# M660X.net
KiCad netlist of a schematic drawn in EAGLE
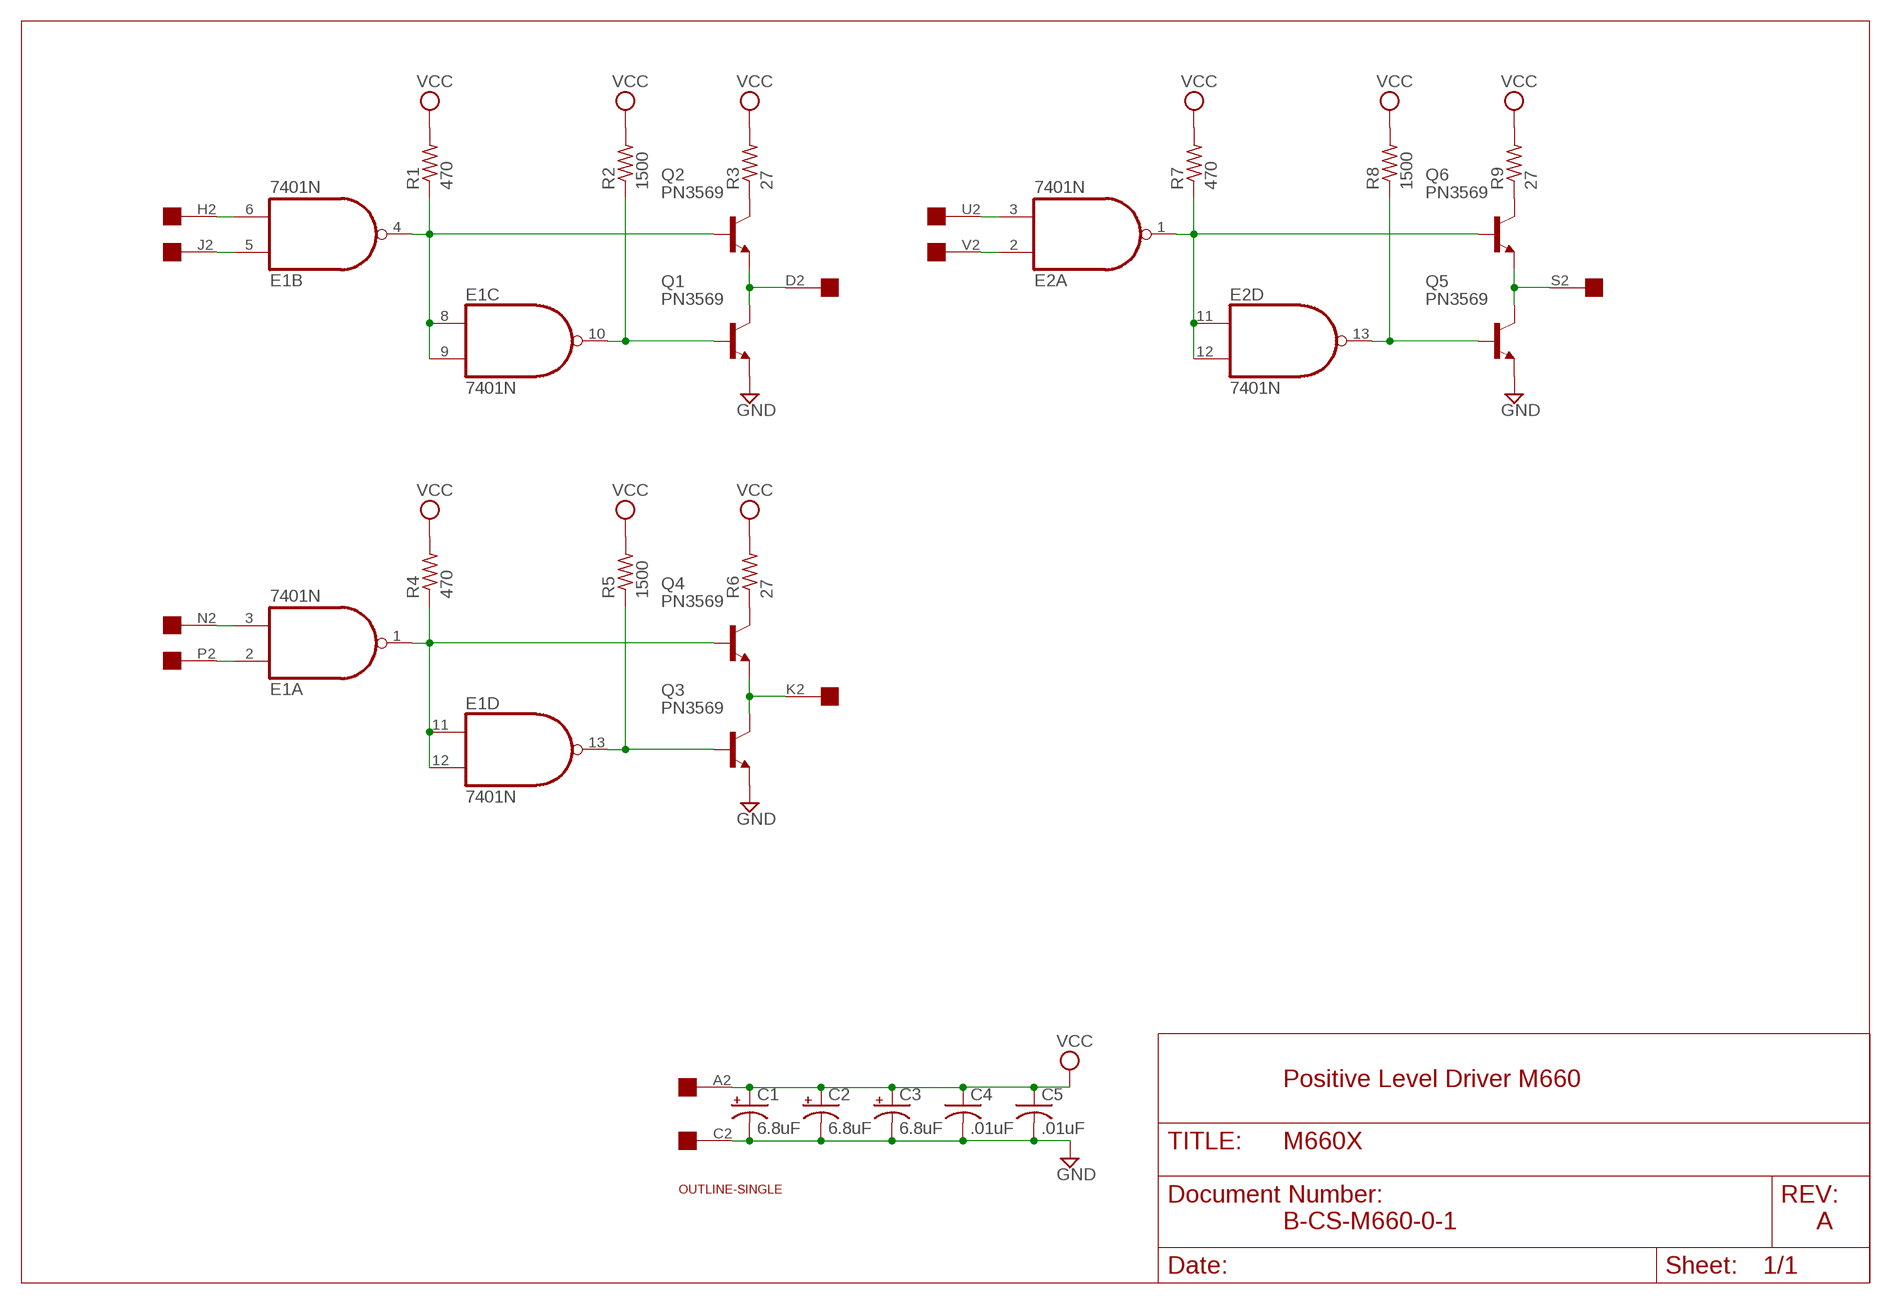
[diagram p0: schematic, sheet 1]

(export (version "E")
  (design (tool "Eeschema 10.0.6"))
  (components
    (comp (ref "C1")
      (value "6.8uF")
      (footprint "eagle-import:E15-5")
      (libsource (lib "eagle-import") (part "CPOL-USE15-5AXIAL"))
    )
    (comp (ref "C2")
      (value "6.8uF")
      (footprint "eagle-import:E15-5")
      (libsource (lib "eagle-import") (part "CPOL-USE15-5AXIAL"))
    )
    (comp (ref "C3")
      (value "6.8uF")
      (footprint "eagle-import:E15-5")
      (libsource (lib "eagle-import") (part "CPOL-USE15-5AXIAL"))
    )
    (comp (ref "C4")
      (value ".01uF")
      (footprint "eagle-import:C050-025X075")
      (libsource (lib "eagle-import") (part "C-US050-025X075"))
    )
    (comp (ref "C5")
      (value ".01uF")
      (footprint "eagle-import:C050-025X075")
      (libsource (lib "eagle-import") (part "C-US050-025X075"))
    )
    (comp (ref "E1")
      (value "7401N")
      (footprint "eagle-import:DIL14")
      (libsource (lib "eagle-import") (part "7401NLS"))
    )
    (comp (ref "E2")
      (value "7401N")
      (footprint "eagle-import:DIL14")
      (libsource (lib "eagle-import") (part "7401NLS"))
    )
    (comp (ref "Q1")
      (value "PN3569")
      (footprint "eagle-import:TO5")
      (libsource (lib "eagle-import") (part "2N2219"))
    )
    (comp (ref "Q2")
      (value "PN3569")
      (footprint "eagle-import:TO5")
      (libsource (lib "eagle-import") (part "2N2219"))
    )
    (comp (ref "Q3")
      (value "PN3569")
      (footprint "eagle-import:TO5")
      (libsource (lib "eagle-import") (part "2N2219"))
    )
    (comp (ref "Q4")
      (value "PN3569")
      (footprint "eagle-import:TO5")
      (libsource (lib "eagle-import") (part "2N2219"))
    )
    (comp (ref "Q5")
      (value "PN3569")
      (footprint "eagle-import:TO5")
      (libsource (lib "eagle-import") (part "2N2219"))
    )
    (comp (ref "Q6")
      (value "PN3569")
      (footprint "eagle-import:TO5")
      (libsource (lib "eagle-import") (part "2N2219"))
    )
    (comp (ref "R1")
      (value "470")
      (footprint "eagle-import:0207_10")
      (libsource (lib "eagle-import") (part "R-US_0207/10"))
    )
    (comp (ref "R2")
      (value "1500")
      (footprint "eagle-import:0207_10")
      (libsource (lib "eagle-import") (part "R-US_0207/10"))
    )
    (comp (ref "R3")
      (value "27")
      (footprint "eagle-import:0411_15")
      (libsource (lib "eagle-import") (part "R-US_0411/15"))
    )
    (comp (ref "R4")
      (value "470")
      (footprint "eagle-import:0207_10")
      (libsource (lib "eagle-import") (part "R-US_0207/10"))
    )
    (comp (ref "R5")
      (value "1500")
      (footprint "eagle-import:0207_10")
      (libsource (lib "eagle-import") (part "R-US_0207/10"))
    )
    (comp (ref "R6")
      (value "27")
      (footprint "eagle-import:0411_15")
      (libsource (lib "eagle-import") (part "R-US_0411/15"))
    )
    (comp (ref "R7")
      (value "470")
      (footprint "eagle-import:0207_10")
      (libsource (lib "eagle-import") (part "R-US_0207/10"))
    )
    (comp (ref "R8")
      (value "1500")
      (footprint "eagle-import:0207_10")
      (libsource (lib "eagle-import") (part "R-US_0207/10"))
    )
    (comp (ref "R9")
      (value "27")
      (footprint "eagle-import:0411_15")
      (libsource (lib "eagle-import") (part "R-US_0411/15"))
    )
    (comp (ref "U$1")
      (value "OUTLINE-SINGLE")
      (footprint "eagle-import:SINGLE")
      (libsource (lib "eagle-import") (part "OUTLINE-SINGLE"))
    )
    (comp (ref "U$3")
      (value "EDGE-1")
      (footprint "eagle-import:EDGE-CON1")
      (libsource (lib "eagle-import") (part "EDGE-1"))
    )
  )
  (nets
    (net (code "1") (name "GND") (class "Default")
      (node (ref "C1") (pin "-") (pinfunction "-_-") (pintype "passive"))
      (node (ref "C2") (pin "-") (pinfunction "-_-") (pintype "passive"))
      (node (ref "C3") (pin "-") (pinfunction "-_-") (pintype "passive"))
      (node (ref "C4") (pin "2") (pinfunction "2_2") (pintype "passive"))
      (node (ref "C5") (pin "2") (pinfunction "2_2") (pintype "passive"))
      (node (ref "Q1") (pin "1") (pinfunction "E_1") (pintype "passive"))
      (node (ref "Q3") (pin "1") (pinfunction "E_1") (pintype "passive"))
      (node (ref "Q5") (pin "1") (pinfunction "E_1") (pintype "passive"))
      (node (ref "U$3") (pin "C2") (pinfunction "1_C2") (pintype "bidirectional"))
    )
    (net (code "2") (name "Net-(E1A-I0)") (class "Default")
      (node (ref "E1") (pin "2") (pinfunction "I0_2") (pintype "input"))
      (node (ref "U$3") (pin "P2") (pinfunction "1_P2") (pintype "bidirectional"))
    )
    (net (code "3") (name "Net-(E1A-I1)") (class "Default")
      (node (ref "E1") (pin "3") (pinfunction "I1_3") (pintype "input"))
      (node (ref "U$3") (pin "N2") (pinfunction "1_N2") (pintype "bidirectional"))
    )
    (net (code "4") (name "Net-(E1A-O)") (class "Default")
      (node (ref "E1") (pin "1") (pinfunction "O_1") (pintype "open_collector"))
      (node (ref "E1") (pin "11") (pinfunction "I0_11") (pintype "input"))
      (node (ref "E1") (pin "12") (pinfunction "I1_12") (pintype "input"))
      (node (ref "Q4") (pin "2") (pinfunction "B_2") (pintype "passive"))
      (node (ref "R4") (pin "1") (pinfunction "1_1") (pintype "passive"))
    )
    (net (code "5") (name "Net-(E1B-I0)") (class "Default")
      (node (ref "E1") (pin "5") (pinfunction "I0_5") (pintype "input"))
      (node (ref "U$3") (pin "J2") (pinfunction "1_J2") (pintype "bidirectional"))
    )
    (net (code "6") (name "Net-(E1B-I1)") (class "Default")
      (node (ref "E1") (pin "6") (pinfunction "I1_6") (pintype "input"))
      (node (ref "U$3") (pin "H2") (pinfunction "1_H2") (pintype "bidirectional"))
    )
    (net (code "7") (name "Net-(E1B-O)") (class "Default")
      (node (ref "E1") (pin "4") (pinfunction "O_4") (pintype "open_collector"))
      (node (ref "E1") (pin "8") (pinfunction "I0_8") (pintype "input"))
      (node (ref "E1") (pin "9") (pinfunction "I1_9") (pintype "input"))
      (node (ref "Q2") (pin "2") (pinfunction "B_2") (pintype "passive"))
      (node (ref "R1") (pin "1") (pinfunction "1_1") (pintype "passive"))
    )
    (net (code "8") (name "Net-(E1C-O)") (class "Default")
      (node (ref "E1") (pin "10") (pinfunction "O_10") (pintype "open_collector"))
      (node (ref "Q1") (pin "2") (pinfunction "B_2") (pintype "passive"))
      (node (ref "R2") (pin "1") (pinfunction "1_1") (pintype "passive"))
    )
    (net (code "9") (name "Net-(E1D-O)") (class "Default")
      (node (ref "E1") (pin "13") (pinfunction "O_13") (pintype "open_collector"))
      (node (ref "Q3") (pin "2") (pinfunction "B_2") (pintype "passive"))
      (node (ref "R5") (pin "1") (pinfunction "1_1") (pintype "passive"))
    )
    (net (code "10") (name "Net-(E2A-I0)") (class "Default")
      (node (ref "E2") (pin "2") (pinfunction "I0_2") (pintype "input"))
      (node (ref "U$3") (pin "V2") (pinfunction "1_V2") (pintype "bidirectional"))
    )
    (net (code "11") (name "Net-(E2A-I1)") (class "Default")
      (node (ref "E2") (pin "3") (pinfunction "I1_3") (pintype "input"))
      (node (ref "U$3") (pin "U2") (pinfunction "1_U2") (pintype "bidirectional"))
    )
    (net (code "12") (name "Net-(E2A-O)") (class "Default")
      (node (ref "E2") (pin "1") (pinfunction "O_1") (pintype "open_collector"))
      (node (ref "E2") (pin "11") (pinfunction "I0_11") (pintype "input"))
      (node (ref "E2") (pin "12") (pinfunction "I1_12") (pintype "input"))
      (node (ref "Q6") (pin "2") (pinfunction "B_2") (pintype "passive"))
      (node (ref "R7") (pin "1") (pinfunction "1_1") (pintype "passive"))
    )
    (net (code "13") (name "Net-(E2D-O)") (class "Default")
      (node (ref "E2") (pin "13") (pinfunction "O_13") (pintype "open_collector"))
      (node (ref "Q5") (pin "2") (pinfunction "B_2") (pintype "passive"))
      (node (ref "R8") (pin "1") (pinfunction "1_1") (pintype "passive"))
    )
    (net (code "14") (name "Net-(Q1-C)") (class "Default")
      (node (ref "Q1") (pin "3") (pinfunction "C_3") (pintype "passive"))
      (node (ref "Q2") (pin "1") (pinfunction "E_1") (pintype "passive"))
      (node (ref "U$3") (pin "D2") (pinfunction "1_D2") (pintype "bidirectional"))
    )
    (net (code "15") (name "Net-(Q2-C)") (class "Default")
      (node (ref "Q2") (pin "3") (pinfunction "C_3") (pintype "passive"))
      (node (ref "R3") (pin "1") (pinfunction "1_1") (pintype "passive"))
    )
    (net (code "16") (name "Net-(Q3-C)") (class "Default")
      (node (ref "Q3") (pin "3") (pinfunction "C_3") (pintype "passive"))
      (node (ref "Q4") (pin "1") (pinfunction "E_1") (pintype "passive"))
      (node (ref "U$3") (pin "K2") (pinfunction "1_K2") (pintype "bidirectional"))
    )
    (net (code "17") (name "Net-(Q4-C)") (class "Default")
      (node (ref "Q4") (pin "3") (pinfunction "C_3") (pintype "passive"))
      (node (ref "R6") (pin "1") (pinfunction "1_1") (pintype "passive"))
    )
    (net (code "18") (name "Net-(Q5-C)") (class "Default")
      (node (ref "Q5") (pin "3") (pinfunction "C_3") (pintype "passive"))
      (node (ref "Q6") (pin "1") (pinfunction "E_1") (pintype "passive"))
      (node (ref "U$3") (pin "S2") (pinfunction "1_S2") (pintype "bidirectional"))
    )
    (net (code "19") (name "Net-(Q6-C)") (class "Default")
      (node (ref "Q6") (pin "3") (pinfunction "C_3") (pintype "passive"))
      (node (ref "R9") (pin "1") (pinfunction "1_1") (pintype "passive"))
    )
    (net (code "20") (name "VCC") (class "Default")
      (node (ref "C1") (pin "+") (pinfunction "+_+") (pintype "passive"))
      (node (ref "C2") (pin "+") (pinfunction "+_+") (pintype "passive"))
      (node (ref "C3") (pin "+") (pinfunction "+_+") (pintype "passive"))
      (node (ref "C4") (pin "1") (pinfunction "1_1") (pintype "passive"))
      (node (ref "C5") (pin "1") (pinfunction "1_1") (pintype "passive"))
      (node (ref "R1") (pin "2") (pinfunction "2_2") (pintype "passive"))
      (node (ref "R2") (pin "2") (pinfunction "2_2") (pintype "passive"))
      (node (ref "R3") (pin "2") (pinfunction "2_2") (pintype "passive"))
      (node (ref "R4") (pin "2") (pinfunction "2_2") (pintype "passive"))
      (node (ref "R5") (pin "2") (pinfunction "2_2") (pintype "passive"))
      (node (ref "R6") (pin "2") (pinfunction "2_2") (pintype "passive"))
      (node (ref "R7") (pin "2") (pinfunction "2_2") (pintype "passive"))
      (node (ref "R8") (pin "2") (pinfunction "2_2") (pintype "passive"))
      (node (ref "R9") (pin "2") (pinfunction "2_2") (pintype "passive"))
      (node (ref "U$3") (pin "A2") (pinfunction "1_A2") (pintype "bidirectional"))
    )
  )
)
